# schematic1.net
KiCad netlist of a schematic drawn in EAGLE
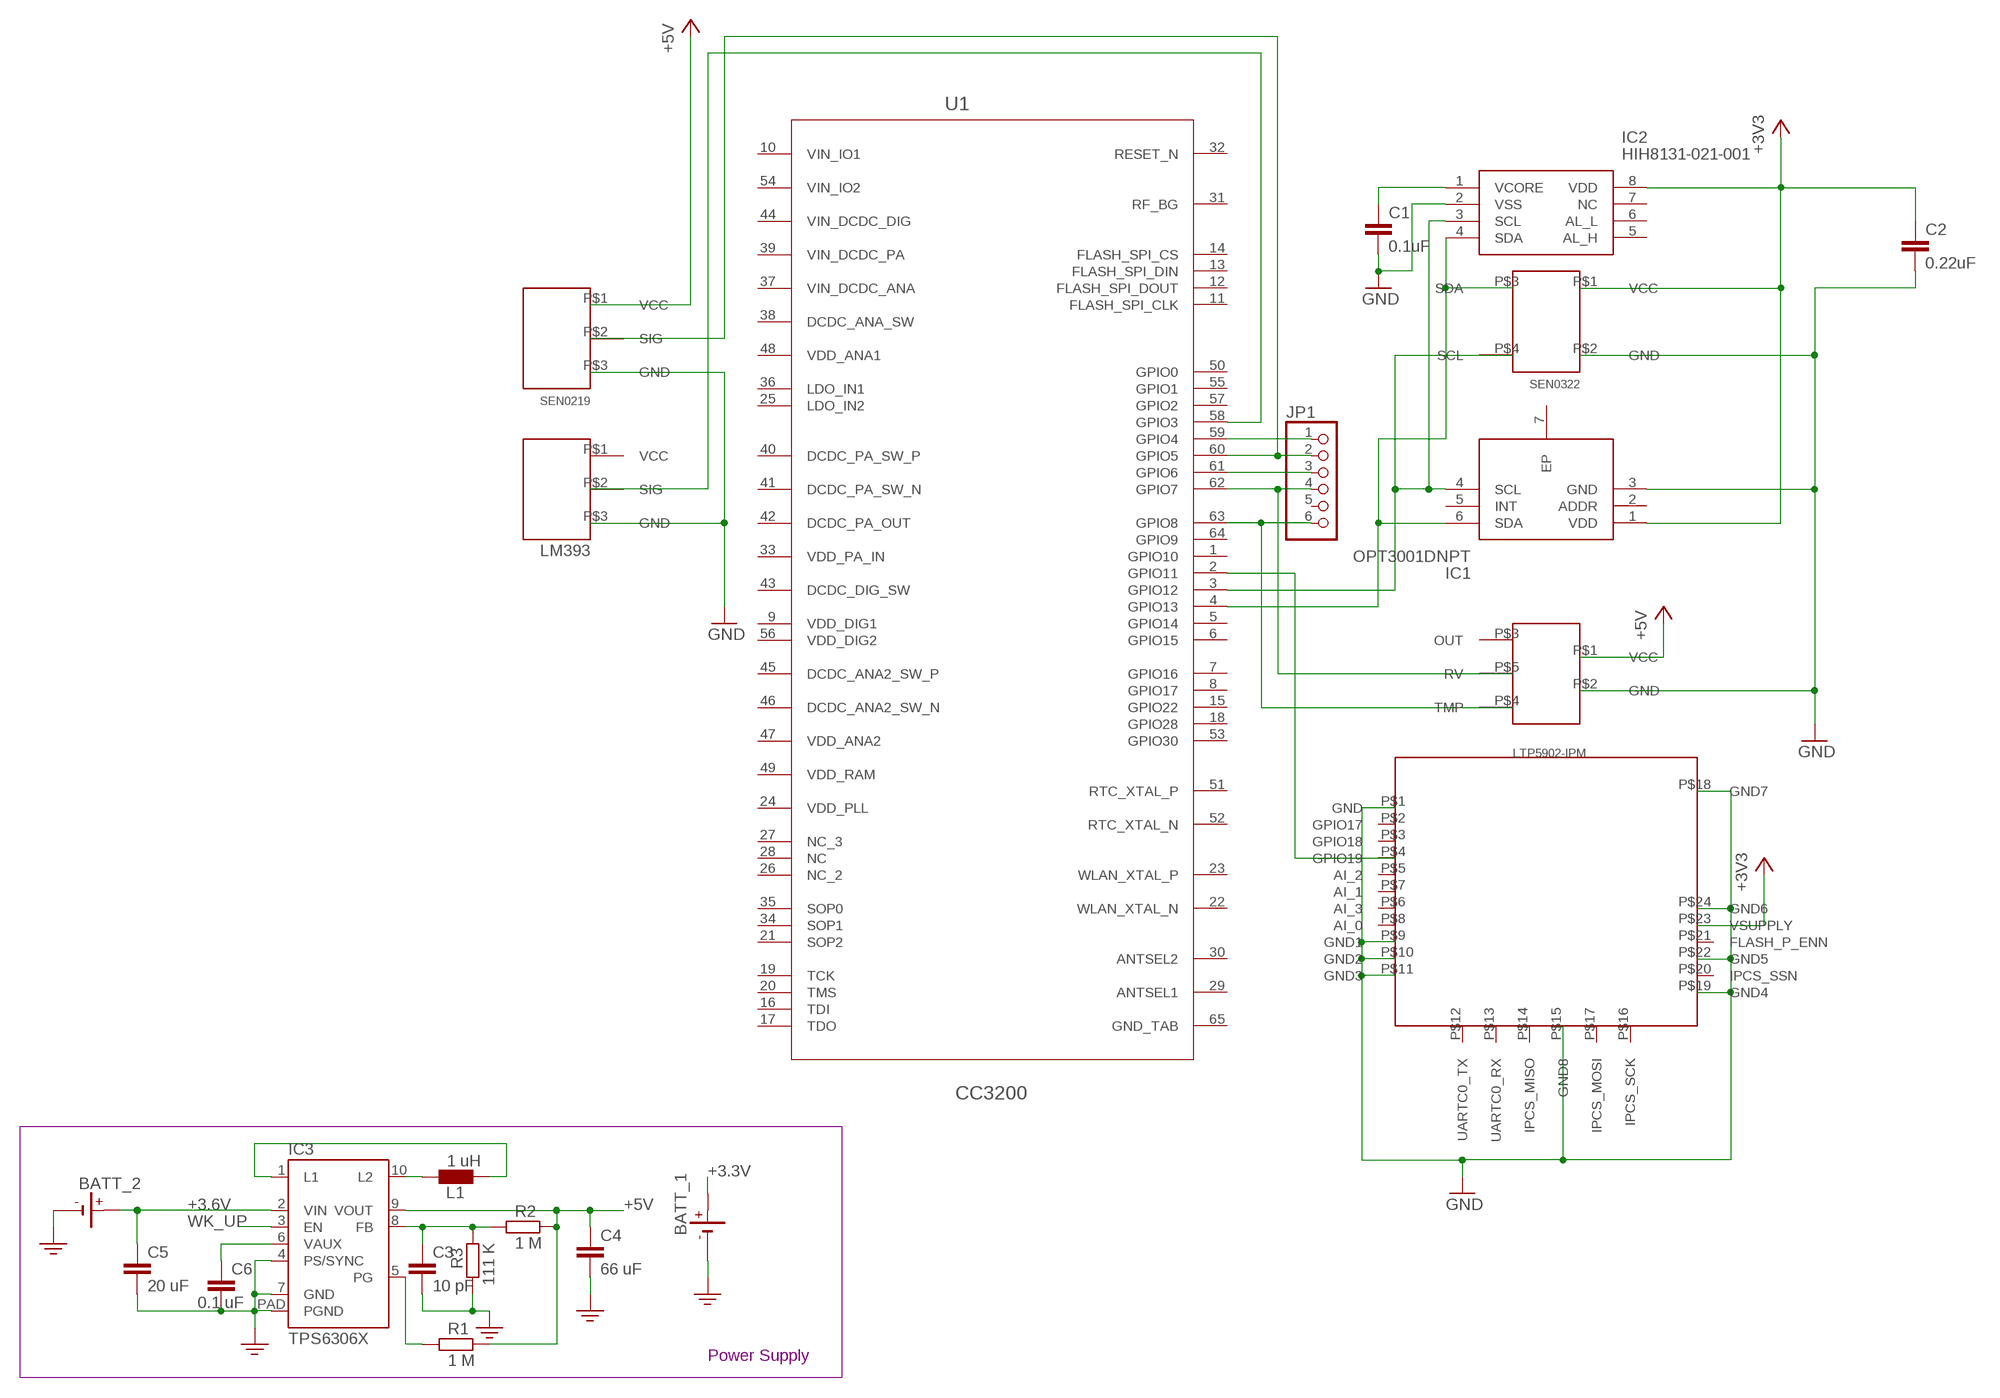
[diagram p0: schematic, sheet 1]

(export (version "E")
  (design (tool "Eeschema 10.0.6"))
  (components
    (comp (ref "BATT_1")
      (value "BATTERY_BR1225/FA")
      (footprint "eagle-import:BATTERY_BR1225_FA")
      (libsource (lib "eagle-import") (part "BATTERY_BR1225/FA"))
    )
    (comp (ref "BATT_2")
      (value "BATTERY_BR1225/FA")
      (footprint "eagle-import:BATTERY_BR1225_FA")
      (libsource (lib "eagle-import") (part "BATTERY_BR1225/FA"))
    )
    (comp (ref "C1")
      (value "0.1uF")
      (footprint "eagle-import:C2.5-2")
      (libsource (lib "eagle-import") (part "C2.5/2"))
    )
    (comp (ref "C2")
      (value "0.22uF")
      (footprint "eagle-import:C2.5-2")
      (libsource (lib "eagle-import") (part "C2.5/2"))
    )
    (comp (ref "C3")
      (value "10 pF")
      (footprint "eagle-import:C1808")
      (libsource (lib "eagle-import") (part "CC1808"))
    )
    (comp (ref "C4")
      (value "66 uF")
      (footprint "eagle-import:C1808")
      (libsource (lib "eagle-import") (part "CC1808"))
    )
    (comp (ref "C5")
      (value "20 uF")
      (footprint "eagle-import:C1808")
      (libsource (lib "eagle-import") (part "CC1808"))
    )
    (comp (ref "C6")
      (value "0.1 uF")
      (footprint "eagle-import:C1808")
      (libsource (lib "eagle-import") (part "CC1808"))
    )
    (comp (ref "IC1")
      (value "OPT3001DNPT")
      (footprint "eagle-import:SON65P200X200X65-7N")
      (fields (field (name "MOUSER_PART_NUMBER") "595-OPT3001DNPT"))
      (libsource (lib "eagle-import") (part "OPT3001DNPT"))
    )
    (comp (ref "IC2")
      (value "HIH8131-021-001")
      (footprint "eagle-import:SOIC127P600X206-8N")
      (fields (field (name "MOUSER_PART_NUMBER") "785-HIH8131-021-001"))
      (libsource (lib "eagle-import") (part "HIH8131-021-001"))
    )
    (comp (ref "IC3")
      (value "TPS6306X")
      (footprint "eagle-import:S-PWSON-N10")
      (libsource (lib "eagle-import") (part "TPS6306X"))
    )
    (comp (ref "JP1")
      (value "PINHD-1X6CB")
      (footprint "eagle-import:1X06-CLEANBIG")
      (libsource (lib "eagle-import") (part "PINHD-1X6CB"))
    )
    (comp (ref "L1")
      (value "1 uH")
      (footprint "eagle-import:0204_7")
      (libsource (lib "eagle-import") (part "L0204/7"))
    )
    (comp (ref "R1")
      (value "1 M")
      (footprint "eagle-import:R2010")
      (libsource (lib "eagle-import") (part "RR2010"))
    )
    (comp (ref "R2")
      (value "1 M")
      (footprint "eagle-import:R2010")
      (libsource (lib "eagle-import") (part "RR2010"))
    )
    (comp (ref "R3")
      (value "111 K")
      (footprint "eagle-import:R2010")
      (libsource (lib "eagle-import") (part "RR2010"))
    )
    (comp (ref "U1")
      (value "CC3200")
      (footprint "eagle-import:RGC0064A")
      (fields
        (field (name "ALTERNATEPARTNUMBER") "CC3200R1M2RGC")
        (field (name "MANUFACTURER") "Texas Instruments")
        (field (name "PARTNUMBER") "CC3200R1M2RGCR")
      )
      (libsource (lib "eagle-import") (part "CC3200R1M2RGCR"))
    )
    (comp (ref "U2")
      (value "WIND")
      (footprint "eagle-import:WIND")
      (libsource (lib "eagle-import") (part "WIND"))
    )
    (comp (ref "U3")
      (value "SEN0322")
      (footprint "eagle-import:SEN0322")
      (libsource (lib "eagle-import") (part "SEN0322"))
    )
    (comp (ref "U4")
      (value "SEN0219")
      (footprint "eagle-import:SEN0219")
      (libsource (lib "eagle-import") (part "SEN0219"))
    )
    (comp (ref "U5")
      (value "LM393")
      (footprint "eagle-import:LM393")
      (libsource (lib "eagle-import") (part "LM393"))
    )
    (comp (ref "U6")
      (value "LTP5902")
      (footprint "eagle-import:LTP5901")
      (libsource (lib "eagle-import") (part "LTP5902"))
    )
  )
  (nets
    (net (code "1") (name "+3V3") (class "Default")
      (node (ref "C2") (pin "1") (pinfunction "1_1") (pintype "passive"))
      (node (ref "IC1") (pin "1") (pinfunction "VDD_1") (pintype "bidirectional"))
      (node (ref "IC2") (pin "8") (pinfunction "VDD_8") (pintype "bidirectional"))
      (node (ref "U3") (pin "P$1") (pinfunction "VCC_P$1") (pintype "bidirectional"))
      (node (ref "U6") (pin "P$23") (pinfunction "VSUPPLY_P$23") (pintype "bidirectional"))
    )
    (net (code "2") (name "+5V") (class "Default")
      (node (ref "C4") (pin "1") (pinfunction "1_1") (pintype "passive"))
      (node (ref "IC3") (pin "9") (pinfunction "VOUT_9") (pintype "passive"))
      (node (ref "R1") (pin "2") (pinfunction "2_2") (pintype "passive"))
      (node (ref "R2") (pin "2") (pinfunction "2_2") (pintype "passive"))
      (node (ref "U2") (pin "P$1") (pinfunction "VCC_P$1") (pintype "bidirectional"))
      (node (ref "U4") (pin "P$1") (pinfunction "VCC_P$1") (pintype "bidirectional"))
    )
    (net (code "3") (name "/+3.3V") (class "Default")
      (node (ref "BATT_1") (pin "+") (pinfunction "+_+") (pintype "passive"))
    )
    (net (code "4") (name "/+3.6V") (class "Default")
      (node (ref "BATT_2") (pin "+") (pinfunction "+_+") (pintype "passive"))
      (node (ref "C5") (pin "1") (pinfunction "1_1") (pintype "passive"))
      (node (ref "IC3") (pin "2") (pinfunction "VIN_2") (pintype "passive"))
    )
    (net (code "5") (name "/DCDC_ANA_SW") (class "Default")
      (node (ref "U1") (pin "38") (pinfunction "DCDC_ANA_SW_38") (pintype "power_in"))
    )
    (net (code "6") (name "/DCDC_DIG_SW") (class "Default")
      (node (ref "U1") (pin "43") (pinfunction "DCDC_DIG_SW_43") (pintype "power_in"))
    )
    (net (code "7") (name "/DCDC_PA_OUT") (class "Default")
      (node (ref "U1") (pin "42") (pinfunction "DCDC_PA_OUT_42") (pintype "power_in"))
    )
    (net (code "8") (name "/DCDC_PA_SW_N") (class "Default")
      (node (ref "U1") (pin "41") (pinfunction "DCDC_PA_SW_N_41") (pintype "power_in"))
    )
    (net (code "9") (name "/DCDC_PA_SW_P") (class "Default")
      (node (ref "U1") (pin "40") (pinfunction "DCDC_PA_SW_P_40") (pintype "power_in"))
    )
    (net (code "10") (name "/GND_TAB") (class "Default")
      (node (ref "U1") (pin "65") (pinfunction "GND_TAB_65") (pintype "power_in"))
    )
    (net (code "11") (name "/LDO_IN1") (class "Default")
      (node (ref "U1") (pin "36") (pinfunction "LDO_IN1_36") (pintype "power_in"))
    )
    (net (code "12") (name "/LDO_IN2") (class "Default")
      (node (ref "U1") (pin "25") (pinfunction "LDO_IN2_25") (pintype "power_in"))
    )
    (net (code "13") (name "/VDD_ANA1") (class "Default")
      (node (ref "U1") (pin "48") (pinfunction "VDD_ANA1_48") (pintype "power_in"))
    )
    (net (code "14") (name "/VDD_ANA2") (class "Default")
      (node (ref "U1") (pin "47") (pinfunction "VDD_ANA2_47") (pintype "power_in"))
    )
    (net (code "15") (name "/VDD_DIG1") (class "Default")
      (node (ref "U1") (pin "9") (pinfunction "VDD_DIG1_9") (pintype "power_in"))
    )
    (net (code "16") (name "/VDD_DIG2") (class "Default")
      (node (ref "U1") (pin "56") (pinfunction "VDD_DIG2_56") (pintype "power_in"))
    )
    (net (code "17") (name "/VDD_PA_IN") (class "Default")
      (node (ref "U1") (pin "33") (pinfunction "VDD_PA_IN_33") (pintype "power_in"))
    )
    (net (code "18") (name "/VDD_PLL") (class "Default")
      (node (ref "U1") (pin "24") (pinfunction "VDD_PLL_24") (pintype "power_in"))
    )
    (net (code "19") (name "/VDD_RAM") (class "Default")
      (node (ref "U1") (pin "49") (pinfunction "VDD_RAM_49") (pintype "power_in"))
    )
    (net (code "20") (name "/VIN_DCDC_ANA") (class "Default")
      (node (ref "U1") (pin "37") (pinfunction "VIN_DCDC_ANA_37") (pintype "power_in"))
    )
    (net (code "21") (name "/VIN_DCDC_DIG") (class "Default")
      (node (ref "U1") (pin "44") (pinfunction "VIN_DCDC_DIG_44") (pintype "power_in"))
    )
    (net (code "22") (name "/VIN_DCDC_PA") (class "Default")
      (node (ref "U1") (pin "39") (pinfunction "VIN_DCDC_PA_39") (pintype "power_in"))
    )
    (net (code "23") (name "/VIN_IO1") (class "Default")
      (node (ref "U1") (pin "10") (pinfunction "VIN_IO1_10") (pintype "power_in"))
    )
    (net (code "24") (name "/VIN_IO2") (class "Default")
      (node (ref "U1") (pin "54") (pinfunction "VIN_IO2_54") (pintype "power_in"))
    )
    (net (code "25") (name "/WK_UP") (class "Default")
      (node (ref "IC3") (pin "3") (pinfunction "EN_3") (pintype "passive"))
    )
    (net (code "26") (name "GND") (class "Default")
      (node (ref "BATT_1") (pin "-") (pinfunction "-_-") (pintype "passive"))
      (node (ref "BATT_2") (pin "-") (pinfunction "-_-") (pintype "passive"))
      (node (ref "C1") (pin "2") (pinfunction "2_2") (pintype "passive"))
      (node (ref "C2") (pin "2") (pinfunction "2_2") (pintype "passive"))
      (node (ref "C3") (pin "2") (pinfunction "2_2") (pintype "passive"))
      (node (ref "C4") (pin "2") (pinfunction "2_2") (pintype "passive"))
      (node (ref "C5") (pin "2") (pinfunction "2_2") (pintype "passive"))
      (node (ref "C6") (pin "2") (pinfunction "2_2") (pintype "passive"))
      (node (ref "IC1") (pin "3") (pinfunction "GND_3") (pintype "bidirectional"))
      (node (ref "IC2") (pin "2") (pinfunction "VSS_2") (pintype "bidirectional"))
      (node (ref "IC3") (pin "4") (pinfunction "PS/SYNC_4") (pintype "passive"))
      (node (ref "IC3") (pin "7") (pinfunction "GND_7") (pintype "passive"))
      (node (ref "IC3") (pin "PAD") (pinfunction "PGND_PAD") (pintype "passive"))
      (node (ref "R3") (pin "1") (pinfunction "1_1") (pintype "passive"))
      (node (ref "U2") (pin "P$2") (pinfunction "GND_P$2") (pintype "bidirectional"))
      (node (ref "U3") (pin "P$2") (pinfunction "GND_P$2") (pintype "bidirectional"))
      (node (ref "U4") (pin "P$3") (pinfunction "GND_P$3") (pintype "bidirectional"))
      (node (ref "U5") (pin "P$3") (pinfunction "GND_P$3") (pintype "bidirectional"))
      (node (ref "U6") (pin "P$1") (pinfunction "GND_P$1") (pintype "bidirectional"))
      (node (ref "U6") (pin "P$10") (pinfunction "GND2_P$10") (pintype "bidirectional"))
      (node (ref "U6") (pin "P$11") (pinfunction "GND3_P$11") (pintype "bidirectional"))
      (node (ref "U6") (pin "P$15") (pinfunction "GND8_P$15") (pintype "bidirectional"))
      (node (ref "U6") (pin "P$18") (pinfunction "GND7_P$18") (pintype "bidirectional"))
      (node (ref "U6") (pin "P$19") (pinfunction "GND4_P$19") (pintype "bidirectional"))
      (node (ref "U6") (pin "P$22") (pinfunction "GND5_P$22") (pintype "bidirectional"))
      (node (ref "U6") (pin "P$24") (pinfunction "GND6_P$24") (pintype "bidirectional"))
      (node (ref "U6") (pin "P$9") (pinfunction "GND1_P$9") (pintype "bidirectional"))
    )
    (net (code "27") (name "Net-(IC1-SCL)") (class "Default")
      (node (ref "IC1") (pin "4") (pinfunction "SCL_4") (pintype "bidirectional"))
      (node (ref "IC2") (pin "3") (pinfunction "SCL_3") (pintype "bidirectional"))
      (node (ref "U1") (pin "3") (pinfunction "GPIO12_3") (pintype "bidirectional"))
      (node (ref "U3") (pin "P$4") (pinfunction "SCL_P$4") (pintype "bidirectional"))
    )
    (net (code "28") (name "Net-(IC1-SDA)") (class "Default")
      (node (ref "IC1") (pin "6") (pinfunction "SDA_6") (pintype "bidirectional"))
      (node (ref "IC2") (pin "4") (pinfunction "SDA_4") (pintype "bidirectional"))
      (node (ref "U1") (pin "4") (pinfunction "GPIO13_4") (pintype "bidirectional"))
      (node (ref "U3") (pin "P$3") (pinfunction "SDA_P$3") (pintype "bidirectional"))
    )
    (net (code "29") (name "Net-(IC2-VCORE)") (class "Default")
      (node (ref "C1") (pin "1") (pinfunction "1_1") (pintype "passive"))
      (node (ref "IC2") (pin "1") (pinfunction "VCORE_1") (pintype "bidirectional"))
    )
    (net (code "30") (name "Net-(IC3-FB)") (class "Default")
      (node (ref "C3") (pin "1") (pinfunction "1_1") (pintype "passive"))
      (node (ref "IC3") (pin "8") (pinfunction "FB_8") (pintype "passive"))
      (node (ref "R2") (pin "1") (pinfunction "1_1") (pintype "passive"))
      (node (ref "R3") (pin "2") (pinfunction "2_2") (pintype "passive"))
    )
    (net (code "31") (name "Net-(IC3-L1)") (class "Default")
      (node (ref "IC3") (pin "1") (pinfunction "L1_1") (pintype "passive"))
      (node (ref "L1") (pin "2") (pinfunction "2_2") (pintype "passive"))
    )
    (net (code "32") (name "Net-(IC3-L2)") (class "Default")
      (node (ref "IC3") (pin "10") (pinfunction "L2_10") (pintype "passive"))
      (node (ref "L1") (pin "1") (pinfunction "1_1") (pintype "passive"))
    )
    (net (code "33") (name "Net-(IC3-PG)") (class "Default")
      (node (ref "IC3") (pin "5") (pinfunction "PG_5") (pintype "passive"))
      (node (ref "R1") (pin "1") (pinfunction "1_1") (pintype "passive"))
    )
    (net (code "34") (name "Net-(IC3-VAUX)") (class "Default")
      (node (ref "C6") (pin "1") (pinfunction "1_1") (pintype "passive"))
      (node (ref "IC3") (pin "6") (pinfunction "VAUX_6") (pintype "passive"))
    )
    (net (code "35") (name "Net-(U1-GPIO3)") (class "Default")
      (node (ref "U1") (pin "58") (pinfunction "GPIO3_58") (pintype "bidirectional"))
      (node (ref "U5") (pin "P$2") (pinfunction "SIG_P$2") (pintype "bidirectional"))
    )
    (net (code "36") (name "Net-(U1-GPIO4)") (class "Default")
      (node (ref "JP1") (pin "1") (pinfunction "1_1") (pintype "passive"))
      (node (ref "U1") (pin "59") (pinfunction "GPIO4_59") (pintype "bidirectional"))
    )
    (net (code "37") (name "Net-(U1-GPIO5)") (class "Default")
      (node (ref "JP1") (pin "2") (pinfunction "2_2") (pintype "passive"))
      (node (ref "U1") (pin "60") (pinfunction "GPIO5_60") (pintype "bidirectional"))
      (node (ref "U4") (pin "P$2") (pinfunction "SIG_P$2") (pintype "bidirectional"))
    )
    (net (code "38") (name "Net-(U1-GPIO6)") (class "Default")
      (node (ref "JP1") (pin "3") (pinfunction "3_3") (pintype "passive"))
      (node (ref "U1") (pin "61") (pinfunction "GPIO6_61") (pintype "bidirectional"))
    )
    (net (code "39") (name "Net-(U1-GPIO7)") (class "Default")
      (node (ref "JP1") (pin "4") (pinfunction "4_4") (pintype "passive"))
      (node (ref "U1") (pin "62") (pinfunction "GPIO7_62") (pintype "bidirectional"))
      (node (ref "U2") (pin "P$5") (pinfunction "RV_P$5") (pintype "bidirectional"))
    )
    (net (code "40") (name "Net-(U1-GPIO8)") (class "Default")
      (node (ref "JP1") (pin "6") (pinfunction "6_6") (pintype "passive"))
      (node (ref "U1") (pin "63") (pinfunction "GPIO8_63") (pintype "bidirectional"))
      (node (ref "U2") (pin "P$4") (pinfunction "TMP_P$4") (pintype "bidirectional"))
    )
    (net (code "41") (name "Net-(U1-GPIO11)") (class "Default")
      (node (ref "U1") (pin "2") (pinfunction "GPIO11_2") (pintype "bidirectional"))
      (node (ref "U6") (pin "P$4") (pinfunction "GPIO19_P$4") (pintype "bidirectional"))
    )
    (net (code "42") (name "unconnected-(IC1-ADDR-Pad2)") (class "Default")
      (node (ref "IC1") (pin "2") (pinfunction "ADDR_2") (pintype "bidirectional"))
    )
    (net (code "43") (name "unconnected-(IC1-EP-Pad7)") (class "Default")
      (node (ref "IC1") (pin "7") (pinfunction "EP_7") (pintype "bidirectional"))
    )
    (net (code "44") (name "unconnected-(IC1-INT-Pad5)") (class "Default")
      (node (ref "IC1") (pin "5") (pinfunction "INT_5") (pintype "bidirectional"))
    )
    (net (code "45") (name "unconnected-(IC2-AL_H-Pad5)") (class "Default")
      (node (ref "IC2") (pin "5") (pinfunction "AL_H_5") (pintype "bidirectional"))
    )
    (net (code "46") (name "unconnected-(IC2-AL_L-Pad6)") (class "Default")
      (node (ref "IC2") (pin "6") (pinfunction "AL_L_6") (pintype "bidirectional"))
    )
    (net (code "47") (name "unconnected-(IC2-NC-Pad7)") (class "Default")
      (node (ref "IC2") (pin "7") (pinfunction "NC_7") (pintype "no_connect"))
    )
    (net (code "48") (name "unconnected-(JP1-Pad5)") (class "Default")
      (node (ref "JP1") (pin "5") (pinfunction "5_5") (pintype "passive"))
    )
    (net (code "49") (name "unconnected-(U1-ANTSEL1-Pad29)") (class "Default")
      (node (ref "U1") (pin "29") (pinfunction "ANTSEL1_29") (pintype "output"))
    )
    (net (code "50") (name "unconnected-(U1-ANTSEL2-Pad30)") (class "Default")
      (node (ref "U1") (pin "30") (pinfunction "ANTSEL2_30") (pintype "output"))
    )
    (net (code "51") (name "unconnected-(U1-DCDC_ANA2_SW_N-Pad46)") (class "Default")
      (node (ref "U1") (pin "46") (pinfunction "DCDC_ANA2_SW_N_46") (pintype "bidirectional"))
    )
    (net (code "52") (name "unconnected-(U1-DCDC_ANA2_SW_P-Pad45)") (class "Default")
      (node (ref "U1") (pin "45") (pinfunction "DCDC_ANA2_SW_P_45") (pintype "bidirectional"))
    )
    (net (code "53") (name "unconnected-(U1-FLASH_SPI_CLK-Pad11)") (class "Default")
      (node (ref "U1") (pin "11") (pinfunction "FLASH_SPI_CLK_11") (pintype "output"))
    )
    (net (code "54") (name "unconnected-(U1-FLASH_SPI_CS-Pad14)") (class "Default")
      (node (ref "U1") (pin "14") (pinfunction "FLASH_SPI_CS_14") (pintype "output"))
    )
    (net (code "55") (name "unconnected-(U1-FLASH_SPI_DIN-Pad13)") (class "Default")
      (node (ref "U1") (pin "13") (pinfunction "FLASH_SPI_DIN_13") (pintype "input"))
    )
    (net (code "56") (name "unconnected-(U1-FLASH_SPI_DOUT-Pad12)") (class "Default")
      (node (ref "U1") (pin "12") (pinfunction "FLASH_SPI_DOUT_12") (pintype "output"))
    )
    (net (code "57") (name "unconnected-(U1-GPIO0-Pad50)") (class "Default")
      (node (ref "U1") (pin "50") (pinfunction "GPIO0_50") (pintype "bidirectional"))
    )
    (net (code "58") (name "unconnected-(U1-GPIO1-Pad55)") (class "Default")
      (node (ref "U1") (pin "55") (pinfunction "GPIO1_55") (pintype "bidirectional"))
    )
    (net (code "59") (name "unconnected-(U1-GPIO2-Pad57)") (class "Default")
      (node (ref "U1") (pin "57") (pinfunction "GPIO2_57") (pintype "bidirectional"))
    )
    (net (code "60") (name "unconnected-(U1-GPIO9-Pad64)") (class "Default")
      (node (ref "U1") (pin "64") (pinfunction "GPIO9_64") (pintype "bidirectional"))
    )
    (net (code "61") (name "unconnected-(U1-GPIO10-Pad1)") (class "Default")
      (node (ref "U1") (pin "1") (pinfunction "GPIO10_1") (pintype "bidirectional"))
    )
    (net (code "62") (name "unconnected-(U1-GPIO14-Pad5)") (class "Default")
      (node (ref "U1") (pin "5") (pinfunction "GPIO14_5") (pintype "bidirectional"))
    )
    (net (code "63") (name "unconnected-(U1-GPIO15-Pad6)") (class "Default")
      (node (ref "U1") (pin "6") (pinfunction "GPIO15_6") (pintype "bidirectional"))
    )
    (net (code "64") (name "unconnected-(U1-GPIO16-Pad7)") (class "Default")
      (node (ref "U1") (pin "7") (pinfunction "GPIO16_7") (pintype "bidirectional"))
    )
    (net (code "65") (name "unconnected-(U1-GPIO17-Pad8)") (class "Default")
      (node (ref "U1") (pin "8") (pinfunction "GPIO17_8") (pintype "bidirectional"))
    )
    (net (code "66") (name "unconnected-(U1-GPIO22-Pad15)") (class "Default")
      (node (ref "U1") (pin "15") (pinfunction "GPIO22_15") (pintype "bidirectional"))
    )
    (net (code "67") (name "unconnected-(U1-GPIO28-Pad18)") (class "Default")
      (node (ref "U1") (pin "18") (pinfunction "GPIO28_18") (pintype "bidirectional"))
    )
    (net (code "68") (name "unconnected-(U1-GPIO30-Pad53)") (class "Default")
      (node (ref "U1") (pin "53") (pinfunction "GPIO30_53") (pintype "bidirectional"))
    )
    (net (code "69") (name "unconnected-(U1-NC-Pad28)") (class "Default")
      (node (ref "U1") (pin "28") (pinfunction "NC_28") (pintype "passive"))
    )
    (net (code "70") (name "unconnected-(U1-NC_2-Pad26)") (class "Default")
      (node (ref "U1") (pin "26") (pinfunction "NC_2_26") (pintype "passive"))
    )
    (net (code "71") (name "unconnected-(U1-NC_3-Pad27)") (class "Default")
      (node (ref "U1") (pin "27") (pinfunction "NC_3_27") (pintype "passive"))
    )
    (net (code "72") (name "unconnected-(U1-RESET_N-Pad32)") (class "Default")
      (node (ref "U1") (pin "32") (pinfunction "RESET_N_32") (pintype "input"))
    )
    (net (code "73") (name "unconnected-(U1-RF_BG-Pad31)") (class "Default")
      (node (ref "U1") (pin "31") (pinfunction "RF_BG_31") (pintype "passive"))
    )
    (net (code "74") (name "unconnected-(U1-RTC_XTAL_N-Pad52)") (class "Default")
      (node (ref "U1") (pin "52") (pinfunction "RTC_XTAL_N_52") (pintype "passive"))
    )
    (net (code "75") (name "unconnected-(U1-RTC_XTAL_P-Pad51)") (class "Default")
      (node (ref "U1") (pin "51") (pinfunction "RTC_XTAL_P_51") (pintype "passive"))
    )
    (net (code "76") (name "unconnected-(U1-SOP0-Pad35)") (class "Default")
      (node (ref "U1") (pin "35") (pinfunction "SOP0_35") (pintype "input"))
    )
    (net (code "77") (name "unconnected-(U1-SOP1-Pad34)") (class "Default")
      (node (ref "U1") (pin "34") (pinfunction "SOP1_34") (pintype "input"))
    )
    (net (code "78") (name "unconnected-(U1-SOP2-Pad21)") (class "Default")
      (node (ref "U1") (pin "21") (pinfunction "SOP2_21") (pintype "output"))
    )
    (net (code "79") (name "unconnected-(U1-TCK-Pad19)") (class "Default")
      (node (ref "U1") (pin "19") (pinfunction "TCK_19") (pintype "bidirectional"))
    )
    (net (code "80") (name "unconnected-(U1-TDI-Pad16)") (class "Default")
      (node (ref "U1") (pin "16") (pinfunction "TDI_16") (pintype "bidirectional"))
    )
    (net (code "81") (name "unconnected-(U1-TDO-Pad17)") (class "Default")
      (node (ref "U1") (pin "17") (pinfunction "TDO_17") (pintype "bidirectional"))
    )
    (net (code "82") (name "unconnected-(U1-TMS-Pad20)") (class "Default")
      (node (ref "U1") (pin "20") (pinfunction "TMS_20") (pintype "bidirectional"))
    )
    (net (code "83") (name "unconnected-(U1-WLAN_XTAL_N-Pad22)") (class "Default")
      (node (ref "U1") (pin "22") (pinfunction "WLAN_XTAL_N_22") (pintype "passive"))
    )
    (net (code "84") (name "unconnected-(U1-WLAN_XTAL_P-Pad23)") (class "Default")
      (node (ref "U1") (pin "23") (pinfunction "WLAN_XTAL_P_23") (pintype "passive"))
    )
    (net (code "85") (name "unconnected-(U2-OUT-PadP$3)") (class "Default")
      (node (ref "U2") (pin "P$3") (pinfunction "OUT_P$3") (pintype "bidirectional"))
    )
    (net (code "86") (name "unconnected-(U5-VCC-PadP$1)") (class "Default")
      (node (ref "U5") (pin "P$1") (pinfunction "VCC_P$1") (pintype "bidirectional"))
    )
    (net (code "87") (name "unconnected-(U6-AI_0-PadP$8)") (class "Default")
      (node (ref "U6") (pin "P$8") (pinfunction "AI_0_P$8") (pintype "bidirectional"))
    )
    (net (code "88") (name "unconnected-(U6-AI_1-PadP$7)") (class "Default")
      (node (ref "U6") (pin "P$7") (pinfunction "AI_1_P$7") (pintype "bidirectional"))
    )
    (net (code "89") (name "unconnected-(U6-AI_2-PadP$5)") (class "Default")
      (node (ref "U6") (pin "P$5") (pinfunction "AI_2_P$5") (pintype "bidirectional"))
    )
    (net (code "90") (name "unconnected-(U6-AI_3-PadP$6)") (class "Default")
      (node (ref "U6") (pin "P$6") (pinfunction "AI_3_P$6") (pintype "bidirectional"))
    )
    (net (code "91") (name "unconnected-(U6-FLASH_P_ENN-PadP$21)") (class "Default")
      (node (ref "U6") (pin "P$21") (pinfunction "FLASH_P_ENN_P$21") (pintype "bidirectional"))
    )
    (net (code "92") (name "unconnected-(U6-GPIO17-PadP$2)") (class "Default")
      (node (ref "U6") (pin "P$2") (pinfunction "GPIO17_P$2") (pintype "bidirectional"))
    )
    (net (code "93") (name "unconnected-(U6-GPIO18-PadP$3)") (class "Default")
      (node (ref "U6") (pin "P$3") (pinfunction "GPIO18_P$3") (pintype "bidirectional"))
    )
    (net (code "94") (name "unconnected-(U6-IPCS_MISO-PadP$14)") (class "Default")
      (node (ref "U6") (pin "P$14") (pinfunction "IPCS_MISO_P$14") (pintype "bidirectional"))
    )
    (net (code "95") (name "unconnected-(U6-IPCS_MOSI-PadP$17)") (class "Default")
      (node (ref "U6") (pin "P$17") (pinfunction "IPCS_MOSI_P$17") (pintype "bidirectional"))
    )
    (net (code "96") (name "unconnected-(U6-IPCS_SCK-PadP$16)") (class "Default")
      (node (ref "U6") (pin "P$16") (pinfunction "IPCS_SCK_P$16") (pintype "bidirectional"))
    )
    (net (code "97") (name "unconnected-(U6-IPCS_SSN-PadP$20)") (class "Default")
      (node (ref "U6") (pin "P$20") (pinfunction "IPCS_SSN_P$20") (pintype "bidirectional"))
    )
    (net (code "98") (name "unconnected-(U6-UARTC0_RX-PadP$13)") (class "Default")
      (node (ref "U6") (pin "P$13") (pinfunction "UARTC0_RX_P$13") (pintype "bidirectional"))
    )
    (net (code "99") (name "unconnected-(U6-UARTC0_TX-PadP$12)") (class "Default")
      (node (ref "U6") (pin "P$12") (pinfunction "UARTC0_TX_P$12") (pintype "bidirectional"))
    )
  )
)
